# Spectrum_Shield.net
KiCad netlist of a schematic drawn in EAGLE
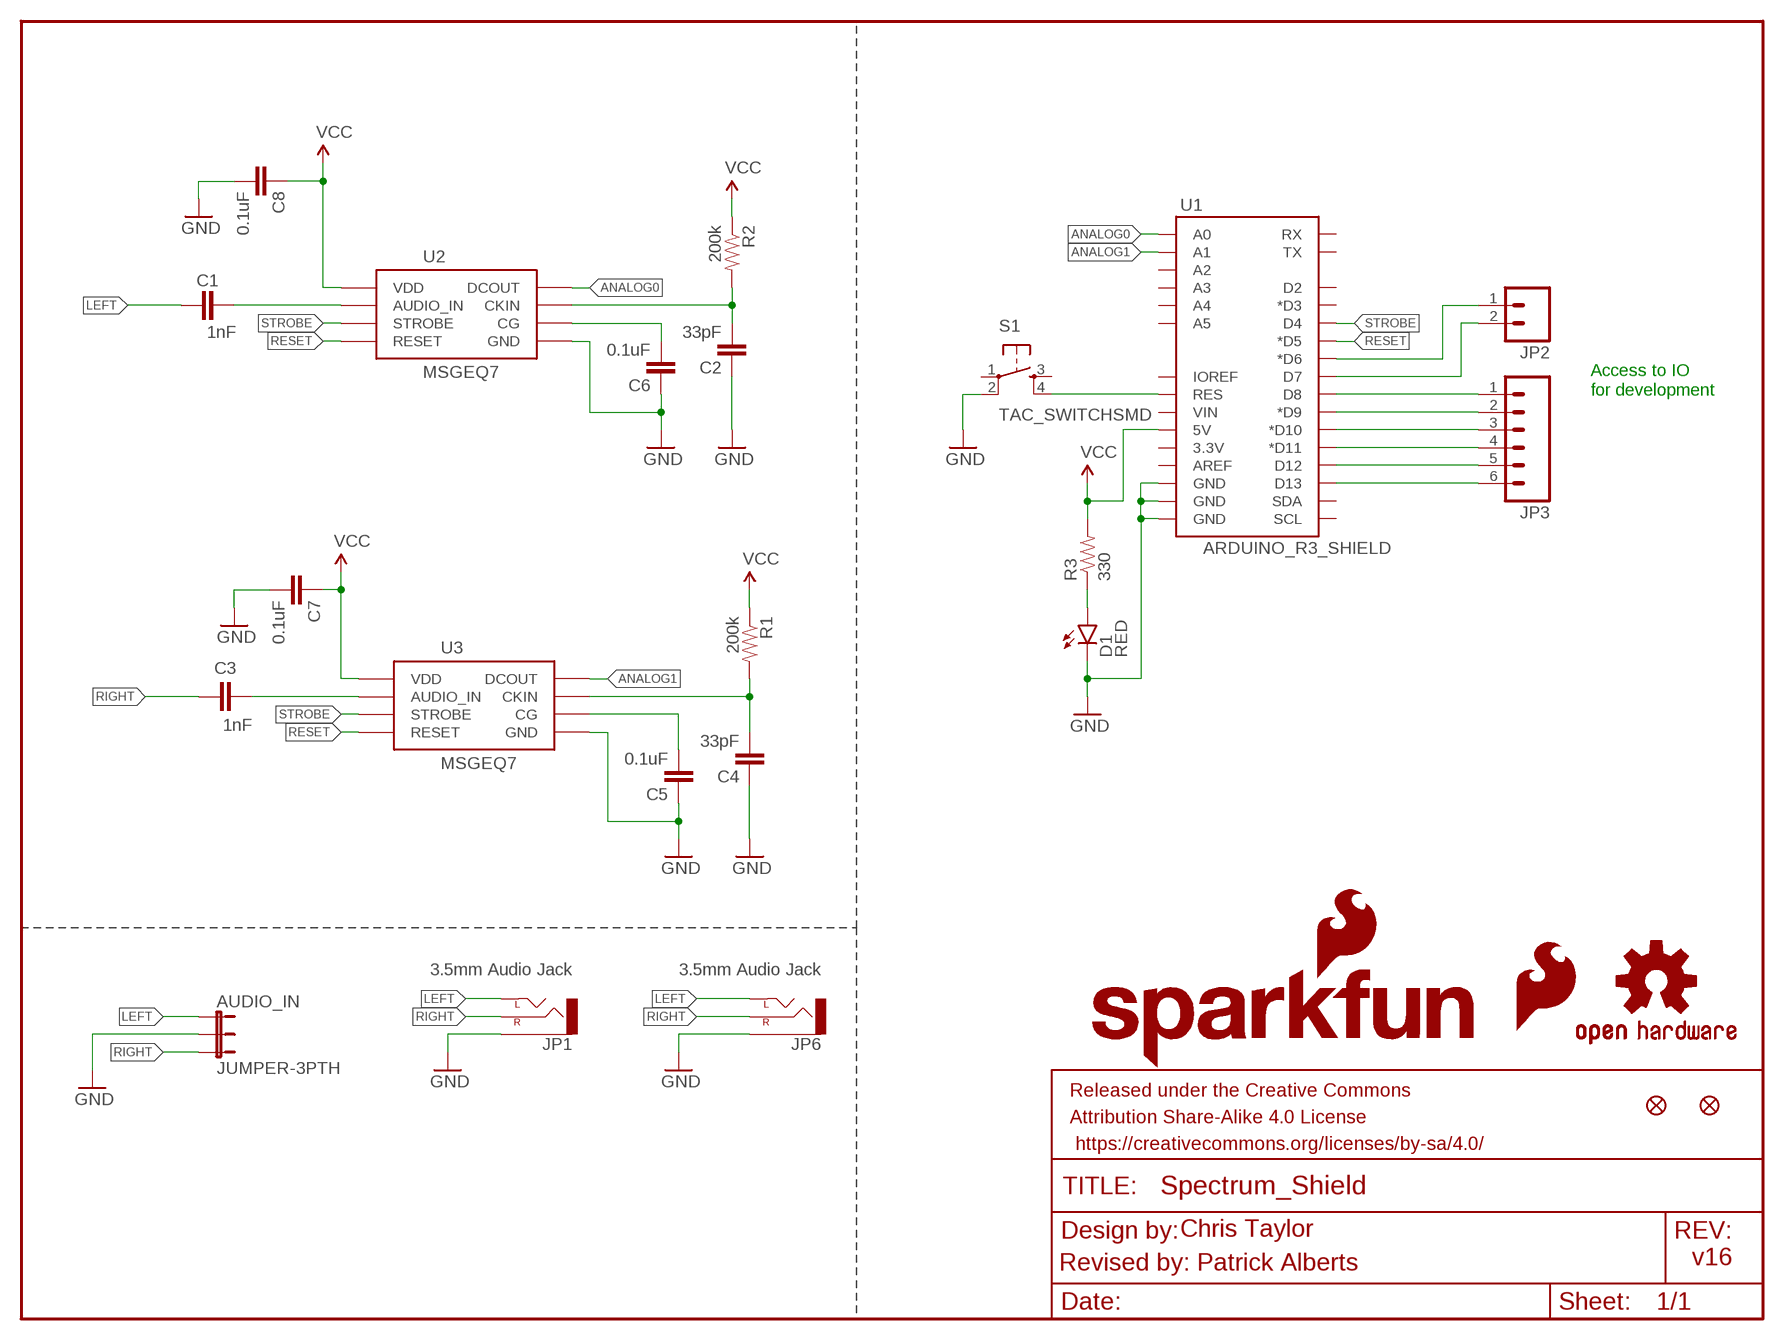
[diagram p0: schematic, sheet 1]

(export (version "E")
  (design (tool "Eeschema 10.0.6"))
  (components
    (comp (ref "AUDIO_IN")
      (value "JUMPER-3PTH")
      (footprint "eagle-import:1X03")
      (libsource (lib "eagle-import") (part "JUMPER-3PTH"))
    )
    (comp (ref "C1")
      (value "1nF")
      (footprint "eagle-import:0603-CAP")
      (libsource (lib "eagle-import") (part "1NF/1000PF-50V-10%(0603)"))
    )
    (comp (ref "C2")
      (value "33pF")
      (footprint "eagle-import:0603-CAP")
      (libsource (lib "eagle-import") (part "33PF-50V-5%-(0603)"))
    )
    (comp (ref "C3")
      (value "1nF")
      (footprint "eagle-import:0603-CAP")
      (libsource (lib "eagle-import") (part "1NF/1000PF-50V-10%(0603)"))
    )
    (comp (ref "C4")
      (value "33pF")
      (footprint "eagle-import:0603-CAP")
      (libsource (lib "eagle-import") (part "33PF-50V-5%-(0603)"))
    )
    (comp (ref "C5")
      (value "0.1uF")
      (footprint "eagle-import:0603-CAP")
      (libsource (lib "eagle-import") (part "0.1UF-25V(+80/-20%)(0603)"))
    )
    (comp (ref "C6")
      (value "0.1uF")
      (footprint "eagle-import:0603-CAP")
      (libsource (lib "eagle-import") (part "0.1UF-25V(+80/-20%)(0603)"))
    )
    (comp (ref "C7")
      (value "0.1uF")
      (footprint "eagle-import:0603-CAP")
      (libsource (lib "eagle-import") (part "0.1UF-25V(+80/-20%)(0603)"))
    )
    (comp (ref "C8")
      (value "0.1uF")
      (footprint "eagle-import:0603-CAP")
      (libsource (lib "eagle-import") (part "0.1UF-25V(+80/-20%)(0603)"))
    )
    (comp (ref "D1")
      (value "RED")
      (footprint "eagle-import:LED-0603")
      (libsource (lib "eagle-import") (part "LED-RED0603"))
    )
    (comp (ref "FRAME1")
      (value "FRAME-LETTER")
      (footprint "eagle-import:CREATIVE_COMMONS")
      (libsource (lib "eagle-import") (part "FRAME-LETTER"))
    )
    (comp (ref "JP1")
      (value "3.5mm Audio Jack")
      (footprint "eagle-import:AUDIO-JACK-3.5MM-SMD")
      (libsource (lib "eagle-import") (part "AUDIO-JACKSMD2"))
    )
    (comp (ref "JP2")
      (value "M02PTH")
      (footprint "eagle-import:1X02")
      (libsource (lib "eagle-import") (part "M02PTH"))
    )
    (comp (ref "JP3")
      (value "M06SIP")
      (footprint "eagle-import:1X06")
      (libsource (lib "eagle-import") (part "M06SIP"))
    )
    (comp (ref "JP4")
      (value "FIDUCIAL1X2")
      (footprint "eagle-import:FIDUCIAL-1X2")
      (libsource (lib "eagle-import") (part "FIDUCIAL1X2"))
    )
    (comp (ref "JP5")
      (value "FIDUCIAL1X2")
      (footprint "eagle-import:FIDUCIAL-1X2")
      (libsource (lib "eagle-import") (part "FIDUCIAL1X2"))
    )
    (comp (ref "JP6")
      (value "3.5mm Audio Jack")
      (footprint "eagle-import:AUDIO-JACK-3.5MM-SMD")
      (libsource (lib "eagle-import") (part "AUDIO-JACKSMD2"))
    )
    (comp (ref "LOGO1")
      (value "OSHW-LOGOM")
      (footprint "eagle-import:OSHW-LOGO-M")
      (libsource (lib "eagle-import") (part "OSHW-LOGOM"))
    )
    (comp (ref "LOGO2")
      (value "SFE_LOGO_FLAME.2_INCH")
      (footprint "eagle-import:SFE_LOGO_FLAME_.2")
      (libsource (lib "eagle-import") (part "SFE_LOGO_FLAME.2_INCH"))
    )
    (comp (ref "LOGO3")
      (value "SFE_LOGO_NAME_FLAME.1_INCH")
      (footprint "eagle-import:SFE_LOGO_NAME_FLAME_.1")
      (libsource (lib "eagle-import") (part "SFE_LOGO_NAME_FLAME.1_INCH"))
    )
    (comp (ref "R1")
      (value "200k")
      (footprint "eagle-import:0603-RES")
      (libsource (lib "eagle-import") (part "200KOHM1/10W1%(0603)200K"))
    )
    (comp (ref "R2")
      (value "200k")
      (footprint "eagle-import:0603-RES")
      (libsource (lib "eagle-import") (part "220KOHM1/10W1%(0603)"))
    )
    (comp (ref "R3")
      (value "330")
      (footprint "eagle-import:0603-RES")
      (libsource (lib "eagle-import") (part "330OHM1/10W1%(0603)"))
    )
    (comp (ref "S1")
      (value "TAC_SWITCHSMD")
      (footprint "eagle-import:TACTILE-SWITCH-SMD")
      (libsource (lib "eagle-import") (part "TAC_SWITCHSMD"))
    )
    (comp (ref "U1")
      (value "ARDUINO_R3_SHIELD")
      (footprint "eagle-import:UNO_R3_SHIELD")
      (libsource (lib "eagle-import") (part "ARDUINO_R3_SHIELD"))
    )
    (comp (ref "U2")
      (value "MSGEQ7SOIC")
      (footprint "eagle-import:SOIC8")
      (libsource (lib "eagle-import") (part "MSGEQ7SOIC"))
    )
    (comp (ref "U3")
      (value "MSGEQ7SOIC")
      (footprint "eagle-import:SOIC8")
      (libsource (lib "eagle-import") (part "MSGEQ7SOIC"))
    )
  )
  (nets
    (net (code "1") (name "ANALOG0") (class "Default")
      (node (ref "U1") (pin "A0") (pinfunction "A0_A0") (pintype "bidirectional"))
      (node (ref "U2") (pin "3") (pinfunction "DCOUT_3") (pintype "bidirectional"))
    )
    (net (code "2") (name "ANALOG1") (class "Default")
      (node (ref "U1") (pin "A1") (pinfunction "A1_A1") (pintype "bidirectional"))
      (node (ref "U3") (pin "3") (pinfunction "DCOUT_3") (pintype "bidirectional"))
    )
    (net (code "3") (name "GND") (class "Default")
      (node (ref "AUDIO_IN") (pin "2") (pinfunction "2_2") (pintype "passive"))
      (node (ref "C2") (pin "1") (pinfunction "1_1") (pintype "passive"))
      (node (ref "C4") (pin "1") (pinfunction "1_1") (pintype "passive"))
      (node (ref "C5") (pin "1") (pinfunction "1_1") (pintype "passive"))
      (node (ref "C6") (pin "1") (pinfunction "1_1") (pintype "passive"))
      (node (ref "C7") (pin "2") (pinfunction "2_2") (pintype "passive"))
      (node (ref "C8") (pin "2") (pinfunction "2_2") (pintype "passive"))
      (node (ref "D1") (pin "C") (pinfunction "C_C") (pintype "passive"))
      (node (ref "JP1") (pin "SLEEVE") (pinfunction "SLEEVE_SLEEVE") (pintype "bidirectional"))
      (node (ref "JP6") (pin "SLEEVE") (pinfunction "SLEEVE_SLEEVE") (pintype "bidirectional"))
      (node (ref "S1") (pin "2") (pinfunction "2_2") (pintype "passive"))
      (node (ref "U1") (pin "GND@0") (pinfunction "GND_GND@0") (pintype "bidirectional"))
      (node (ref "U1") (pin "GND@1") (pinfunction "GND_GND@1") (pintype "bidirectional"))
      (node (ref "U1") (pin "GND@2") (pinfunction "GND_GND@2") (pintype "bidirectional"))
      (node (ref "U2") (pin "2") (pinfunction "GND_2") (pintype "bidirectional"))
      (node (ref "U3") (pin "2") (pinfunction "GND_2") (pintype "bidirectional"))
    )
    (net (code "4") (name "LEFT") (class "Default")
      (node (ref "AUDIO_IN") (pin "1") (pinfunction "1_1") (pintype "passive"))
      (node (ref "C1") (pin "1") (pinfunction "1_1") (pintype "passive"))
      (node (ref "JP1") (pin "TIP") (pinfunction "LEFT_TIP") (pintype "bidirectional"))
      (node (ref "JP6") (pin "TIP") (pinfunction "LEFT_TIP") (pintype "bidirectional"))
    )
    (net (code "5") (name "Net-(D1-PadA)") (class "Default")
      (node (ref "D1") (pin "A") (pinfunction "A_A") (pintype "passive"))
      (node (ref "R3") (pin "1") (pinfunction "1_1") (pintype "passive"))
    )
    (net (code "6") (name "Net-(JP2-Pad2)") (class "Default")
      (node (ref "JP2") (pin "2") (pinfunction "2_2") (pintype "passive"))
      (node (ref "U1") (pin "D7") (pinfunction "D7_D7") (pintype "bidirectional"))
    )
    (net (code "7") (name "Net-(JP3-Pad1)") (class "Default")
      (node (ref "JP3") (pin "1") (pinfunction "1_1") (pintype "passive"))
      (node (ref "U1") (pin "D8") (pinfunction "D8_D8") (pintype "bidirectional"))
    )
    (net (code "8") (name "Net-(JP3-Pad5)") (class "Default")
      (node (ref "JP3") (pin "5") (pinfunction "5_5") (pintype "passive"))
      (node (ref "U1") (pin "D12") (pinfunction "D12_D12") (pintype "bidirectional"))
    )
    (net (code "9") (name "Net-(JP3-Pad6)") (class "Default")
      (node (ref "JP3") (pin "6") (pinfunction "6_6") (pintype "passive"))
      (node (ref "U1") (pin "D13") (pinfunction "D13_D13") (pintype "bidirectional"))
    )
    (net (code "10") (name "Net-(S1-Pad4)") (class "Default")
      (node (ref "S1") (pin "4") (pinfunction "4_4") (pintype "passive"))
      (node (ref "U1") (pin "RES") (pinfunction "RES_RES") (pintype "bidirectional"))
    )
    (net (code "11") (name "Net-(U1-*D6)") (class "Default")
      (node (ref "JP2") (pin "1") (pinfunction "1_1") (pintype "passive"))
      (node (ref "U1") (pin "D6") (pinfunction "*D6_D6") (pintype "bidirectional"))
    )
    (net (code "12") (name "Net-(U1-*D9)") (class "Default")
      (node (ref "JP3") (pin "2") (pinfunction "2_2") (pintype "passive"))
      (node (ref "U1") (pin "D9") (pinfunction "*D9_D9") (pintype "bidirectional"))
    )
    (net (code "13") (name "Net-(U1-*D10)") (class "Default")
      (node (ref "JP3") (pin "3") (pinfunction "3_3") (pintype "passive"))
      (node (ref "U1") (pin "D10") (pinfunction "*D10_D10") (pintype "bidirectional"))
    )
    (net (code "14") (name "Net-(U1-*D11)") (class "Default")
      (node (ref "JP3") (pin "4") (pinfunction "4_4") (pintype "passive"))
      (node (ref "U1") (pin "D11") (pinfunction "*D11_D11") (pintype "bidirectional"))
    )
    (net (code "15") (name "Net-(U2-AUDIO_IN)") (class "Default")
      (node (ref "C1") (pin "2") (pinfunction "2_2") (pintype "passive"))
      (node (ref "U2") (pin "5") (pinfunction "AUDIO_IN_5") (pintype "input"))
    )
    (net (code "16") (name "Net-(U2-CG)") (class "Default")
      (node (ref "C6") (pin "2") (pinfunction "2_2") (pintype "passive"))
      (node (ref "U2") (pin "6") (pinfunction "CG_6") (pintype "bidirectional"))
    )
    (net (code "17") (name "Net-(U2-CKIN)") (class "Default")
      (node (ref "C2") (pin "2") (pinfunction "2_2") (pintype "passive"))
      (node (ref "R2") (pin "2") (pinfunction "2_2") (pintype "passive"))
      (node (ref "U2") (pin "8") (pinfunction "CKIN_8") (pintype "bidirectional"))
    )
    (net (code "18") (name "Net-(U3-AUDIO_IN)") (class "Default")
      (node (ref "C3") (pin "2") (pinfunction "2_2") (pintype "passive"))
      (node (ref "U3") (pin "5") (pinfunction "AUDIO_IN_5") (pintype "input"))
    )
    (net (code "19") (name "Net-(U3-CG)") (class "Default")
      (node (ref "C5") (pin "2") (pinfunction "2_2") (pintype "passive"))
      (node (ref "U3") (pin "6") (pinfunction "CG_6") (pintype "bidirectional"))
    )
    (net (code "20") (name "Net-(U3-CKIN)") (class "Default")
      (node (ref "C4") (pin "2") (pinfunction "2_2") (pintype "passive"))
      (node (ref "R1") (pin "2") (pinfunction "2_2") (pintype "passive"))
      (node (ref "U3") (pin "8") (pinfunction "CKIN_8") (pintype "bidirectional"))
    )
    (net (code "21") (name "RESET") (class "Default")
      (node (ref "U1") (pin "D5") (pinfunction "*D5_D5") (pintype "bidirectional"))
      (node (ref "U2") (pin "7") (pinfunction "RESET_7") (pintype "input"))
      (node (ref "U3") (pin "7") (pinfunction "RESET_7") (pintype "input"))
    )
    (net (code "22") (name "RIGHT") (class "Default")
      (node (ref "AUDIO_IN") (pin "3") (pinfunction "3_3") (pintype "passive"))
      (node (ref "C3") (pin "1") (pinfunction "1_1") (pintype "passive"))
      (node (ref "JP1") (pin "RING") (pinfunction "RIGHT_RING") (pintype "bidirectional"))
      (node (ref "JP6") (pin "RING") (pinfunction "RIGHT_RING") (pintype "bidirectional"))
    )
    (net (code "23") (name "STROBE") (class "Default")
      (node (ref "U1") (pin "D4") (pinfunction "D4_D4") (pintype "bidirectional"))
      (node (ref "U2") (pin "4") (pinfunction "STROBE_4") (pintype "input"))
      (node (ref "U3") (pin "4") (pinfunction "STROBE_4") (pintype "input"))
    )
    (net (code "24") (name "VCC") (class "Default")
      (node (ref "C7") (pin "1") (pinfunction "1_1") (pintype "passive"))
      (node (ref "C8") (pin "1") (pinfunction "1_1") (pintype "passive"))
      (node (ref "R1") (pin "1") (pinfunction "1_1") (pintype "passive"))
      (node (ref "R2") (pin "1") (pinfunction "1_1") (pintype "passive"))
      (node (ref "R3") (pin "2") (pinfunction "2_2") (pintype "passive"))
      (node (ref "U1") (pin "5V") (pinfunction "5V_5V") (pintype "bidirectional"))
      (node (ref "U2") (pin "1") (pinfunction "VDD_1") (pintype "input"))
      (node (ref "U3") (pin "1") (pinfunction "VDD_1") (pintype "input"))
    )
    (net (code "25") (name "unconnected-(S1-Pad1)") (class "Default")
      (node (ref "S1") (pin "1") (pinfunction "1_1") (pintype "passive"))
    )
    (net (code "26") (name "unconnected-(S1-Pad3)") (class "Default")
      (node (ref "S1") (pin "3") (pinfunction "3_3") (pintype "passive"))
    )
    (net (code "27") (name "unconnected-(U1-*D3-PadD3)") (class "Default")
      (node (ref "U1") (pin "D3") (pinfunction "*D3_D3") (pintype "bidirectional"))
    )
    (net (code "28") (name "unconnected-(U1-Pad3.3V)") (class "Default")
      (node (ref "U1") (pin "3.3V") (pinfunction "3.3V_3.3V") (pintype "bidirectional"))
    )
    (net (code "29") (name "unconnected-(U1-PadA2)") (class "Default")
      (node (ref "U1") (pin "A2") (pinfunction "A2_A2") (pintype "bidirectional"))
    )
    (net (code "30") (name "unconnected-(U1-PadA3)") (class "Default")
      (node (ref "U1") (pin "A3") (pinfunction "A3_A3") (pintype "bidirectional"))
    )
    (net (code "31") (name "unconnected-(U1-PadA4)") (class "Default")
      (node (ref "U1") (pin "A4") (pinfunction "A4_A4") (pintype "bidirectional"))
    )
    (net (code "32") (name "unconnected-(U1-PadA5)") (class "Default")
      (node (ref "U1") (pin "A5") (pinfunction "A5_A5") (pintype "bidirectional"))
    )
    (net (code "33") (name "unconnected-(U1-PadAREF)") (class "Default")
      (node (ref "U1") (pin "AREF") (pinfunction "AREF_AREF") (pintype "bidirectional"))
    )
    (net (code "34") (name "unconnected-(U1-PadD2)") (class "Default")
      (node (ref "U1") (pin "D2") (pinfunction "D2_D2") (pintype "bidirectional"))
    )
    (net (code "35") (name "unconnected-(U1-PadIOREF)") (class "Default")
      (node (ref "U1") (pin "IOREF") (pinfunction "IOREF_IOREF") (pintype "bidirectional"))
    )
    (net (code "36") (name "unconnected-(U1-PadRX)") (class "Default")
      (node (ref "U1") (pin "RX") (pinfunction "RX_RX") (pintype "bidirectional"))
    )
    (net (code "37") (name "unconnected-(U1-PadSCL)") (class "Default")
      (node (ref "U1") (pin "SCL") (pinfunction "SCL_SCL") (pintype "bidirectional"))
    )
    (net (code "38") (name "unconnected-(U1-PadSDA)") (class "Default")
      (node (ref "U1") (pin "SDA") (pinfunction "SDA_SDA") (pintype "bidirectional"))
    )
    (net (code "39") (name "unconnected-(U1-PadTX)") (class "Default")
      (node (ref "U1") (pin "TX") (pinfunction "TX_TX") (pintype "bidirectional"))
    )
    (net (code "40") (name "unconnected-(U1-PadVIN)") (class "Default")
      (node (ref "U1") (pin "VIN") (pinfunction "VIN_VIN") (pintype "bidirectional"))
    )
  )
)
